# buttons.net
KiCad netlist of a schematic drawn in EAGLE
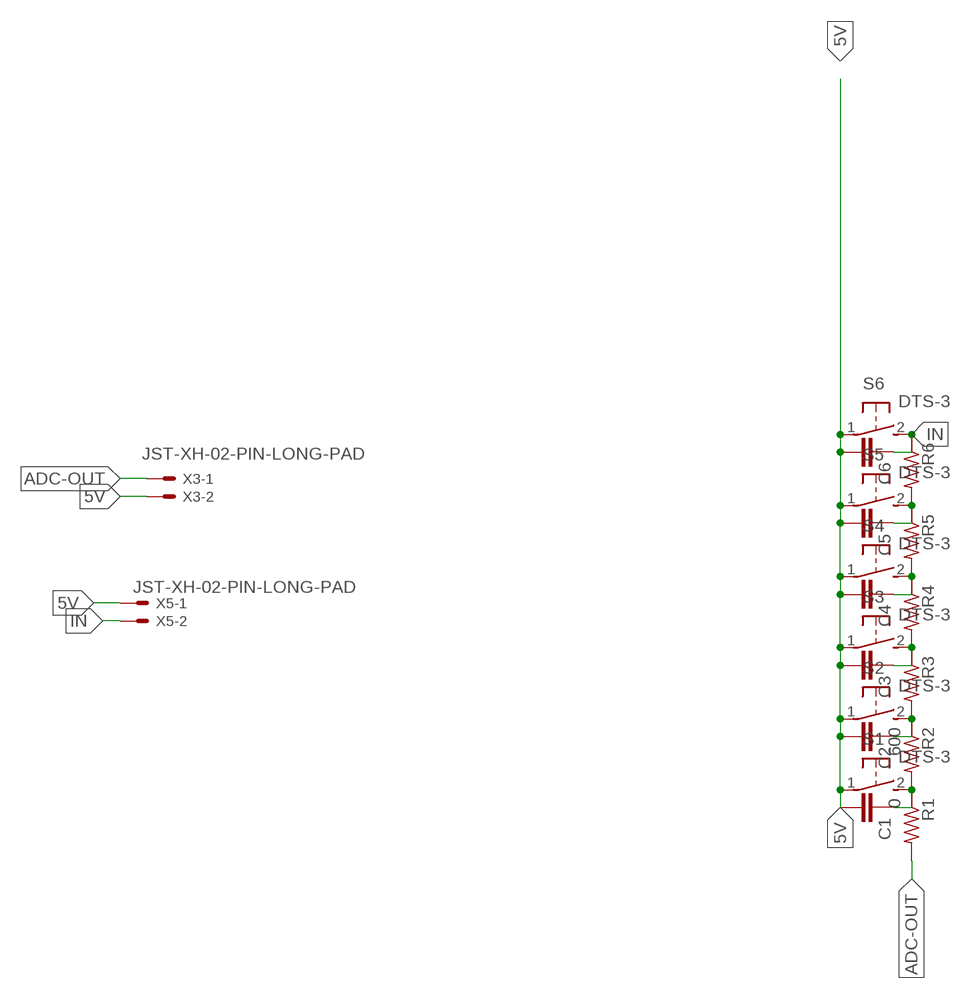
[diagram p0: schematic, sheet 1]

(export (version "E")
  (design (tool "Eeschema 10.0.6"))
  (components
    (comp (ref "C1")
      (value "C-EU025-024X044")
      (footprint "eagle-import:C025-024X044")
      (libsource (lib "eagle-import") (part "C-EU025-024X044"))
    )
    (comp (ref "C2")
      (value "C-EU025-024X044")
      (footprint "eagle-import:C025-024X044")
      (libsource (lib "eagle-import") (part "C-EU025-024X044"))
    )
    (comp (ref "C3")
      (value "C-EU025-024X044")
      (footprint "eagle-import:C025-024X044")
      (libsource (lib "eagle-import") (part "C-EU025-024X044"))
    )
    (comp (ref "C4")
      (value "C-EU025-024X044")
      (footprint "eagle-import:C025-024X044")
      (libsource (lib "eagle-import") (part "C-EU025-024X044"))
    )
    (comp (ref "C5")
      (value "C-EU025-024X044")
      (footprint "eagle-import:C025-024X044")
      (libsource (lib "eagle-import") (part "C-EU025-024X044"))
    )
    (comp (ref "C6")
      (value "C-EU025-024X044")
      (footprint "eagle-import:C025-024X044")
      (libsource (lib "eagle-import") (part "C-EU025-024X044"))
    )
    (comp (ref "R1")
      (value "0")
      (footprint "eagle-import:0204_7")
      (libsource (lib "eagle-import") (part "R-US_0204/7"))
    )
    (comp (ref "R2")
      (value "600")
      (footprint "eagle-import:0204_7")
      (libsource (lib "eagle-import") (part "R-US_0204/7"))
    )
    (comp (ref "R3")
      (value "R-US_0204/7")
      (footprint "eagle-import:0204_7")
      (libsource (lib "eagle-import") (part "R-US_0204/7"))
    )
    (comp (ref "R4")
      (value "R-US_0204/7")
      (footprint "eagle-import:0204_7")
      (libsource (lib "eagle-import") (part "R-US_0204/7"))
    )
    (comp (ref "R5")
      (value "R-US_0204/7")
      (footprint "eagle-import:0204_7")
      (libsource (lib "eagle-import") (part "R-US_0204/7"))
    )
    (comp (ref "R6")
      (value "R-US_0204/7")
      (footprint "eagle-import:0204_7")
      (libsource (lib "eagle-import") (part "R-US_0204/7"))
    )
    (comp (ref "S1")
      (value "DTS-3")
      (footprint "eagle-import:DTS-3")
      (libsource (lib "eagle-import") (part "DTS-3"))
    )
    (comp (ref "S2")
      (value "DTS-3")
      (footprint "eagle-import:DTS-3")
      (libsource (lib "eagle-import") (part "DTS-3"))
    )
    (comp (ref "S3")
      (value "DTS-3")
      (footprint "eagle-import:DTS-3")
      (libsource (lib "eagle-import") (part "DTS-3"))
    )
    (comp (ref "S4")
      (value "DTS-3")
      (footprint "eagle-import:DTS-3")
      (libsource (lib "eagle-import") (part "DTS-3"))
    )
    (comp (ref "S5")
      (value "DTS-3")
      (footprint "eagle-import:DTS-3")
      (libsource (lib "eagle-import") (part "DTS-3"))
    )
    (comp (ref "S6")
      (value "DTS-3")
      (footprint "eagle-import:DTS-3")
      (libsource (lib "eagle-import") (part "DTS-3"))
    )
    (comp (ref "X3")
      (value "JST-XH-02-PIN-LONG-PAD")
      (footprint "eagle-import:JST-XH-02-PACKAGE-LONG-PAD")
      (libsource (lib "eagle-import") (part "JST-XH-02-PIN-LONG-PAD"))
    )
    (comp (ref "X5")
      (value "JST-XH-02-PIN-LONG-PAD")
      (footprint "eagle-import:JST-XH-02-PACKAGE-LONG-PAD")
      (libsource (lib "eagle-import") (part "JST-XH-02-PIN-LONG-PAD"))
    )
  )
  (nets
    (net (code "1") (name "5V") (class "Default")
      (node (ref "C1") (pin "2") (pinfunction "2_2") (pintype "passive"))
      (node (ref "C2") (pin "2") (pinfunction "2_2") (pintype "passive"))
      (node (ref "C3") (pin "2") (pinfunction "2_2") (pintype "passive"))
      (node (ref "C4") (pin "2") (pinfunction "2_2") (pintype "passive"))
      (node (ref "C5") (pin "2") (pinfunction "2_2") (pintype "passive"))
      (node (ref "C6") (pin "2") (pinfunction "2_2") (pintype "passive"))
      (node (ref "S1") (pin "1") (pinfunction "1_1") (pintype "passive"))
      (node (ref "S2") (pin "1") (pinfunction "1_1") (pintype "passive"))
      (node (ref "S3") (pin "1") (pinfunction "1_1") (pintype "passive"))
      (node (ref "S4") (pin "1") (pinfunction "1_1") (pintype "passive"))
      (node (ref "S5") (pin "1") (pinfunction "1_1") (pintype "passive"))
      (node (ref "S6") (pin "1") (pinfunction "1_1") (pintype "passive"))
      (node (ref "X3") (pin "2") (pinfunction "S_2") (pintype "passive"))
      (node (ref "X5") (pin "1") (pinfunction "S_1") (pintype "passive"))
    )
    (net (code "2") (name "ADC-OUT") (class "Default")
      (node (ref "R1") (pin "2") (pinfunction "2_2") (pintype "passive"))
      (node (ref "X3") (pin "1") (pinfunction "S_1") (pintype "passive"))
    )
    (net (code "3") (name "IN") (class "Default")
      (node (ref "C6") (pin "1") (pinfunction "1_1") (pintype "passive"))
      (node (ref "R6") (pin "1") (pinfunction "1_1") (pintype "passive"))
      (node (ref "S6") (pin "2") (pinfunction "2_2") (pintype "passive"))
      (node (ref "X5") (pin "2") (pinfunction "S_2") (pintype "passive"))
    )
    (net (code "4") (name "Net-(C1-Pad1)") (class "Default")
      (node (ref "C1") (pin "1") (pinfunction "1_1") (pintype "passive"))
      (node (ref "R1") (pin "1") (pinfunction "1_1") (pintype "passive"))
      (node (ref "R2") (pin "2") (pinfunction "2_2") (pintype "passive"))
      (node (ref "S1") (pin "2") (pinfunction "2_2") (pintype "passive"))
    )
    (net (code "5") (name "Net-(C2-Pad1)") (class "Default")
      (node (ref "C2") (pin "1") (pinfunction "1_1") (pintype "passive"))
      (node (ref "R2") (pin "1") (pinfunction "1_1") (pintype "passive"))
      (node (ref "R3") (pin "2") (pinfunction "2_2") (pintype "passive"))
      (node (ref "S2") (pin "2") (pinfunction "2_2") (pintype "passive"))
    )
    (net (code "6") (name "Net-(C3-Pad1)") (class "Default")
      (node (ref "C3") (pin "1") (pinfunction "1_1") (pintype "passive"))
      (node (ref "R3") (pin "1") (pinfunction "1_1") (pintype "passive"))
      (node (ref "R4") (pin "2") (pinfunction "2_2") (pintype "passive"))
      (node (ref "S3") (pin "2") (pinfunction "2_2") (pintype "passive"))
    )
    (net (code "7") (name "Net-(C4-Pad1)") (class "Default")
      (node (ref "C4") (pin "1") (pinfunction "1_1") (pintype "passive"))
      (node (ref "R4") (pin "1") (pinfunction "1_1") (pintype "passive"))
      (node (ref "R5") (pin "2") (pinfunction "2_2") (pintype "passive"))
      (node (ref "S4") (pin "2") (pinfunction "2_2") (pintype "passive"))
    )
    (net (code "8") (name "Net-(C5-Pad1)") (class "Default")
      (node (ref "C5") (pin "1") (pinfunction "1_1") (pintype "passive"))
      (node (ref "R5") (pin "1") (pinfunction "1_1") (pintype "passive"))
      (node (ref "R6") (pin "2") (pinfunction "2_2") (pintype "passive"))
      (node (ref "S5") (pin "2") (pinfunction "2_2") (pintype "passive"))
    )
  )
)
